# SCH_Pico-Greenhouse-PCB_2026-05-14.net
KiCad netlist of a schematic drawn in EasyEDA
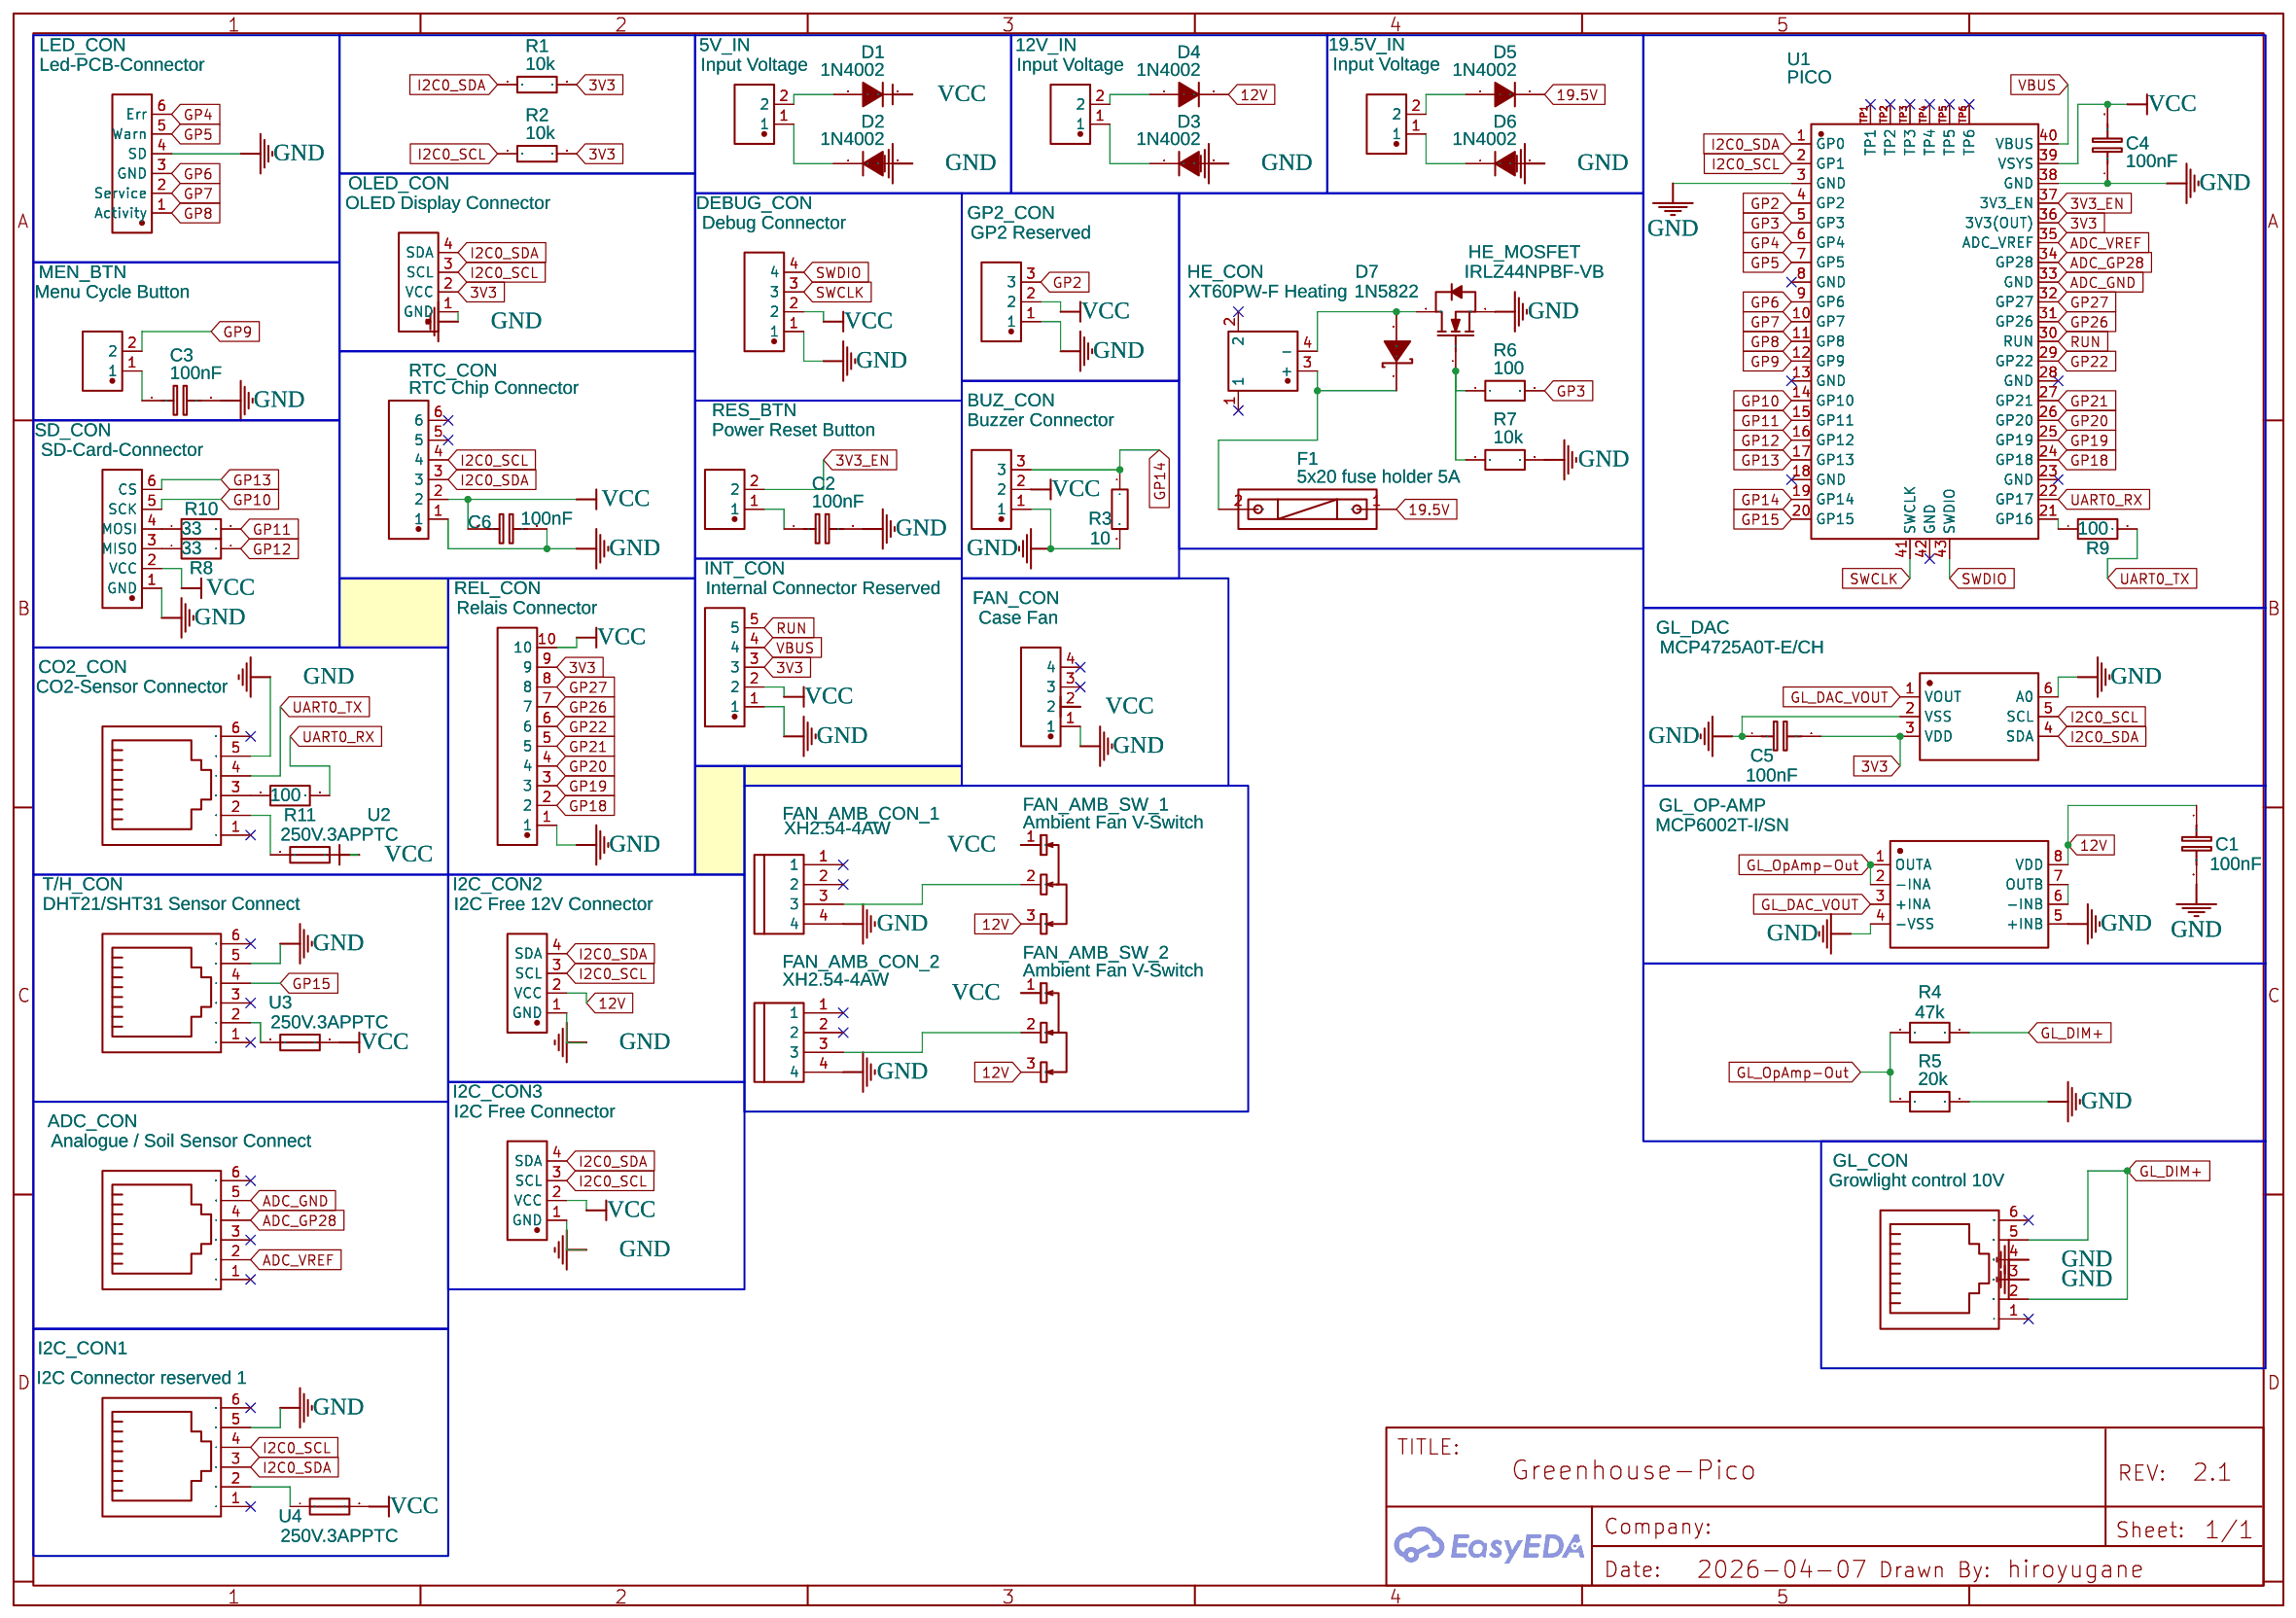
[diagram p0: schematic sheet]

(export (version "E")
  (design (tool "Eeschema 10.0.6"))
  (components
    (comp (ref "5V_IN")
      (value "Input Voltage")
      (fields (field (name "Manufacturer Part") "B2B-XH-A-BK(LF)(SN)") (field (name "Manufacturer") "JST"))
      (libsource (lib "") (part "B2B-XH-A-BK(LF)(SN)_3"))
    )
    (comp (ref "12V_IN")
      (value "Input Voltage")
      (fields (field (name "Manufacturer Part") "B2B-XH-A-BK(LF)(SN)") (field (name "Manufacturer") "JST"))
      (libsource (lib "") (part "B2B-XH-A-BK(LF)(SN)_2"))
    )
    (comp (ref "19.5V_IN")
      (value "Input Voltage")
      (fields
        (field (name "Manufacturer Part") "1935161")
        (field (name "Manufacturer") "Phoenix Contact(菲尼克斯)")
      )
      (libsource (lib "") (part "1935161"))
    )
    (comp (ref "ADC_CON")
      (value "Analogue / Soil Sensor Connect")
      (fields (field (name "Manufacturer Part") "955012661") (field (name "Manufacturer") "MOLEX"))
      (libsource (lib "") (part "95501-2661_1"))
    )
    (comp (ref "BUZ_CON")
      (value "Buzzer Connector")
      (fields (field (name "Manufacturer Part") "B3B-XH-A-BK(LF)(SN)") (field (name "Manufacturer") "JST"))
      (libsource (lib "") (part "B3B-XH-A-BK(LF)(SN)_1"))
    )
    (comp (ref "C1") (value "100nF") (libsource (lib "") (part "C_0603_EU_4")))
    (comp (ref "C2") (value "100nF") (libsource (lib "") (part "C_0603_EU_3")))
    (comp (ref "C3") (value "100nF") (libsource (lib "") (part "C_0603_EU")))
    (comp (ref "C4") (value "100nF") (libsource (lib "") (part "C_0603_EU_2")))
    (comp (ref "C5") (value "100nF") (libsource (lib "") (part "C_0603_EU_1")))
    (comp (ref "C6") (value "100nF") (libsource (lib "") (part "C_0603_EU_3")))
    (comp (ref "CO2_CON")
      (value "CO2-Sensor Connector")
      (fields (field (name "Manufacturer Part") "955012661") (field (name "Manufacturer") "MOLEX"))
      (libsource (lib "") (part "95501-2661_2"))
    )
    (comp (ref "D1")
      (value "1N4002")
      (fields (field (name "Manufacturer Part") "1N4002-E3/54") (field (name "Manufacturer") "VISHAY(威世)"))
      (libsource (lib "") (part "1N4002-E3/54"))
    )
    (comp (ref "D2")
      (value "1N4002")
      (fields (field (name "Manufacturer Part") "1N4002-E3/54") (field (name "Manufacturer") "VISHAY(威世)"))
      (libsource (lib "") (part "1N4002-E3/54_1"))
    )
    (comp (ref "D3")
      (value "1N4002")
      (fields (field (name "Manufacturer Part") "1N4002-E3/54") (field (name "Manufacturer") "VISHAY(威世)"))
      (libsource (lib "") (part "1N4002-E3/54_1"))
    )
    (comp (ref "D4")
      (value "1N4002")
      (fields (field (name "Manufacturer Part") "1N4002-E3/54") (field (name "Manufacturer") "VISHAY(威世)"))
      (libsource (lib "") (part "1N4002-E3/54"))
    )
    (comp (ref "D5")
      (value "1N4002")
      (fields (field (name "Manufacturer Part") "1N4002-E3/54") (field (name "Manufacturer") "VISHAY(威世)"))
      (libsource (lib "") (part "1N4002-E3/54"))
    )
    (comp (ref "D6")
      (value "1N4002")
      (fields (field (name "Manufacturer Part") "1N4002-E3/54") (field (name "Manufacturer") "VISHAY(威世)"))
      (libsource (lib "") (part "1N4002-E3/54_1"))
    )
    (comp (ref "D7")
      (value "1N5822")
      (fields (field (name "Manufacturer") "MDD(辰达半导体)"))
      (libsource (lib "") (part "1N5822"))
    )
    (comp (ref "DEBUG_CON")
      (value "Debug Connector")
      (fields (field (name "Manufacturer Part") "B4B-XH-A-R(LF)(SN)") (field (name "Manufacturer") "JST"))
      (libsource (lib "") (part "B4B-XH-A-R(LF)(SN)_1"))
    )
    (comp (ref "F1")
      (value "5x20 fuse holder 5A")
      (fields
        (field (name "Manufacturer Part") "5x20 BLX-A型 保险丝支架 XC-7")
        (field (name "Manufacturer") "xcfuse(旭程)")
      )
      (libsource (lib "") (part "5x20 BLX-Atype Fuse holder XC-7"))
    )
    (comp (ref "FAN_AMB_CON_1")
      (value "XH2.54-4AW")
      (fields (field (name "Manufacturer Part") "XH-4AW") (field (name "Manufacturer") "BOOMELE(博穆精密)"))
      (libsource (lib "") (part "XH2.54-4AW"))
    )
    (comp (ref "FAN_AMB_CON_2")
      (value "XH2.54-4AW")
      (fields (field (name "Manufacturer Part") "XH-4AW") (field (name "Manufacturer") "BOOMELE(博穆精密)"))
      (libsource (lib "") (part "XH2.54-4AW"))
    )
    (comp (ref "FAN_AMB_SW_1")
      (value "Ambient Fan V-Switch")
      (fields
        (field (name "Manufacturer Part") "MST-12D18G4 SPDT Slide Switch")
        (field (name "Manufacturer") "SHOU HAN(首韩)")
      )
      (libsource (lib "") (part "MST-12D18G4 SPDT SLIDE SWITCH"))
    )
    (comp (ref "FAN_AMB_SW_2")
      (value "Ambient Fan V-Switch")
      (fields
        (field (name "Manufacturer Part") "MST-12D18G4 SPDT Slide Switch")
        (field (name "Manufacturer") "SHOU HAN(首韩)")
      )
      (libsource (lib "") (part "MST-12D18G4 SPDT SLIDE SWITCH"))
    )
    (comp (ref "FAN_CON")
      (value "Case Fan")
      (fields (field (name "Manufacturer Part") "B4B-XH-A-R(LF)(SN)") (field (name "Manufacturer") "JST"))
      (libsource (lib "") (part "B4B-XH-A-R(LF)(SN)"))
    )
    (comp (ref "GL_CON")
      (value "Growlight control 10V")
      (fields (field (name "Manufacturer Part") "955012661") (field (name "Manufacturer") "MOLEX"))
      (libsource (lib "") (part "95501-2661_3"))
    )
    (comp (ref "GL_DAC")
      (value "MCP4725A0T-E/CH")
      (fields (field (name "Manufacturer") "MICROCHIP(美国微芯)"))
      (libsource (lib "") (part "MCP4725A0T-E/CH"))
    )
    (comp (ref "GL_OP-AMP")
      (value "MCP6002T-I/SN")
      (fields (field (name "Manufacturer") "MICROCHIP(美国微芯)"))
      (libsource (lib "") (part "MCP6002T-I/SN"))
    )
    (comp (ref "GP2_CON")
      (value "GP2 Reserved")
      (fields (field (name "Manufacturer Part") "B3B-XH-A-BK(LF)(SN)") (field (name "Manufacturer") "JST"))
      (libsource (lib "") (part "B3B-XH-A-BK(LF)(SN)"))
    )
    (comp (ref "HE_CON")
      (value "XT60PW-F Heating")
      (fields (field (name "Manufacturer Part") "XT60PW-F") (field (name "Manufacturer") "AMASS(艾迈斯)"))
      (libsource (lib "") (part "XT60PW-F_C428722"))
    )
    (comp (ref "HE_MOSFET")
      (value "IRLZ44NPBF-VB")
      (fields (field (name "Manufacturer") "VBsemi(微碧半导体)"))
      (libsource (lib "") (part "IRLZ44NPBF-VB"))
    )
    (comp (ref "I2C_CON1")
      (value "I2C Connector reserved 1")
      (fields (field (name "Manufacturer Part") "955012661") (field (name "Manufacturer") "MOLEX"))
      (libsource (lib "") (part "95501-2661"))
    )
    (comp (ref "I2C_CON2")
      (value "I2C Free 12V Connector")
      (fields (field (name "Manufacturer Part") "B4B-XH-A-R(LF)(SN)") (field (name "Manufacturer") "JST"))
      (libsource (lib "") (part "B4B-XH-A-R(LF)(SN)_3"))
    )
    (comp (ref "I2C_CON3")
      (value "I2C Free Connector")
      (fields (field (name "Manufacturer Part") "B4B-XH-A-R(LF)(SN)") (field (name "Manufacturer") "JST"))
      (libsource (lib "") (part "B4B-XH-A-R(LF)(SN)_3"))
    )
    (comp (ref "INT_CON")
      (value "Internal Connector Reserved")
      (fields (field (name "Manufacturer Part") "B5B-XH-A-M(LF)(SN)") (field (name "Manufacturer") "JST"))
      (libsource (lib "") (part "B5B-XH-A-M(LF)(SN)"))
    )
    (comp (ref "LED_CON")
      (value "Led-PCB-Connector")
      (fields (field (name "Manufacturer Part") "B6B-EH(LF)(SN)") (field (name "Manufacturer") "JST"))
      (libsource (lib "") (part "B6B-EH(LF)(SN)"))
    )
    (comp (ref "MEN_BTN")
      (value "Menu Cycle Button")
      (fields (field (name "Manufacturer Part") "B2B-XH-A-BK(LF)(SN)") (field (name "Manufacturer") "JST"))
      (libsource (lib "") (part "B2B-XH-A-BK(LF)(SN)_1"))
    )
    (comp (ref "OLED_CON")
      (value "OLED Display Connector")
      (fields (field (name "Manufacturer Part") "B4B-XH-A-R(LF)(SN)") (field (name "Manufacturer") "JST"))
      (libsource (lib "") (part "B4B-XH-A-R(LF)(SN)_2"))
    )
    (comp (ref "R1")
      (value "10k")
      (fields (field (name "Manufacturer") "Made in China"))
      (libsource (lib "") (part "330Ω (331) ±5%"))
    )
    (comp (ref "R2")
      (value "10k")
      (fields (field (name "Manufacturer") "Made in China"))
      (libsource (lib "") (part "330Ω (331) ±5%"))
    )
    (comp (ref "R3")
      (value "10")
      (fields (field (name "Manufacturer") "Made in China"))
      (libsource (lib "") (part "330Ω (331) ±5%_1"))
    )
    (comp (ref "R4") (value "47k") (libsource (lib "") (part "R_0603_EU")))
    (comp (ref "R5") (value "20k") (libsource (lib "") (part "R_0603_EU")))
    (comp (ref "R6") (value "100") (libsource (lib "") (part "R_0603_EU")))
    (comp (ref "R7") (value "10k") (libsource (lib "") (part "R_0603_EU_1")))
    (comp (ref "R8") (value "33") (libsource (lib "") (part "R_0603_EU")))
    (comp (ref "R9") (value "100") (libsource (lib "") (part "R_0603_EU")))
    (comp (ref "R10") (value "33") (libsource (lib "") (part "R_0603_EU")))
    (comp (ref "R11") (value "100") (libsource (lib "") (part "R_0603_EU")))
    (comp (ref "REL_CON")
      (value "Relais Connector")
      (fields (field (name "Manufacturer Part") "B10B-EH(LF)(SN)") (field (name "Manufacturer") "JST"))
      (libsource (lib "") (part "B10B-EH(LF)(SN)"))
    )
    (comp (ref "RES_BTN")
      (value "Power Reset Button")
      (fields (field (name "Manufacturer Part") "B2B-XH-A-BK(LF)(SN)") (field (name "Manufacturer") "JST"))
      (libsource (lib "") (part "B2B-XH-A-BK(LF)(SN)"))
    )
    (comp (ref "RTC_CON")
      (value "RTC Chip Connector")
      (fields
        (field (name "Manufacturer Part") "ZX-PM2.54-1-6PY")
        (field (name "Manufacturer") "Megastar(兆星)")
      )
      (libsource (lib "") (part "ZX-PM2.54-1-6PY"))
    )
    (comp (ref "SD_CON")
      (value "SD-Card-Connector")
      (fields (field (name "Manufacturer Part") "B6B-EH(LF)(SN)") (field (name "Manufacturer") "JST"))
      (libsource (lib "") (part "B6B-EH(LF)(SN)_1"))
    )
    (comp (ref "T/H_CON")
      (value "DHT21/SHT31 Sensor Connect")
      (fields (field (name "Manufacturer Part") "955012661") (field (name "Manufacturer") "MOLEX"))
      (libsource (lib "") (part "95501-2661_4"))
    )
    (comp (ref "U1")
      (value "PICO")
      (fields (field (name "Manufacturer") "Raspberry Pi(树莓派)"))
      (libsource (lib "") (part "PICO"))
    )
    (comp (ref "U2")
      (value "250V.3APPTC")
      (fields (field (name "Manufacturer Part") "30V3APPTC"))
      (libsource (lib "") (part "30V3APPTC"))
    )
    (comp (ref "U3")
      (value "250V.3APPTC")
      (fields (field (name "Manufacturer Part") "30V3APPTC"))
      (libsource (lib "") (part "30V3APPTC"))
    )
    (comp (ref "U4")
      (value "250V.3APPTC")
      (fields (field (name "Manufacturer Part") "30V3APPTC"))
      (libsource (lib "") (part "30V3APPTC"))
    )
  )
  (nets
    (net (code "1") (name "3V3") (class "Default")
      (node (ref "C5") (pin "2") (pinfunction "2_2") (pintype "unspecified"))
      (node (ref "GL_DAC") (pin "3") (pinfunction "VDD_3") (pintype "unspecified"))
      (node (ref "INT_CON") (pin "3") (pinfunction "3_3") (pintype "unspecified"))
      (node (ref "OLED_CON") (pin "2") (pinfunction "VCC_2") (pintype "unspecified"))
      (node (ref "R1") (pin "2") (pinfunction "2_2") (pintype "unspecified"))
      (node (ref "R2") (pin "2") (pinfunction "2_2") (pintype "unspecified"))
      (node (ref "REL_CON") (pin "9") (pinfunction "9_9") (pintype "unspecified"))
      (node (ref "U1") (pin "36") (pinfunction "3V3(OUT)_36") (pintype "unspecified"))
    )
    (net (code "2") (name "3V3_EN") (class "Default")
      (node (ref "RES_BTN") (pin "2") (pinfunction "2_2") (pintype "unspecified"))
      (node (ref "U1") (pin "37") (pinfunction "3V3_EN_37") (pintype "unspecified"))
    )
    (net (code "3") (name "12V") (class "Default")
      (node (ref "C1") (pin "1") (pinfunction "1_1") (pintype "unspecified"))
      (node (ref "D4") (pin "1") (pinfunction "C_1") (pintype "unspecified"))
      (node (ref "FAN_AMB_SW_1") (pin "3") (pinfunction "3_3") (pintype "unspecified"))
      (node (ref "FAN_AMB_SW_2") (pin "3") (pinfunction "3_3") (pintype "unspecified"))
      (node (ref "GL_OP-AMP") (pin "8") (pinfunction "VDD_8") (pintype "unspecified"))
      (node (ref "I2C_CON2") (pin "2") (pinfunction "VCC_2") (pintype "unspecified"))
    )
    (net (code "4") (name "19.5V") (class "Default")
      (node (ref "D5") (pin "1") (pinfunction "C_1") (pintype "unspecified"))
      (node (ref "F1") (pin "1") (pinfunction "1_1") (pintype "unspecified"))
    )
    (net (code "5") (name "ADC_GND") (class "Default")
      (node (ref "ADC_CON") (pin "5") (pinfunction "5_5") (pintype "unspecified"))
      (node (ref "U1") (pin "33") (pinfunction "GND_33") (pintype "unspecified"))
    )
    (net (code "6") (name "ADC_GP28") (class "Default")
      (node (ref "ADC_CON") (pin "4") (pinfunction "4_4") (pintype "unspecified"))
      (node (ref "U1") (pin "34") (pinfunction "GP28_34") (pintype "unspecified"))
    )
    (net (code "7") (name "ADC_VREF") (class "Default")
      (node (ref "ADC_CON") (pin "2") (pinfunction "2_2") (pintype "unspecified"))
      (node (ref "U1") (pin "35") (pinfunction "ADC_VREF_35") (pintype "unspecified"))
    )
    (net (code "8") (name "GL_DAC_VOUT") (class "Default")
      (node (ref "GL_DAC") (pin "1") (pinfunction "VOUT_1") (pintype "unspecified"))
      (node (ref "GL_OP-AMP") (pin "3") (pinfunction "+INA_3") (pintype "unspecified"))
    )
    (net (code "9") (name "GL_DIM+") (class "Default")
      (node (ref "GL_CON") (pin "2") (pinfunction "GL+_2") (pintype "unspecified"))
      (node (ref "GL_CON") (pin "5") (pinfunction "GL+_5") (pintype "unspecified"))
      (node (ref "R4") (pin "2") (pinfunction "2_2") (pintype "unspecified"))
    )
    (net (code "10") (name "GL_OpAmp-Out") (class "Default")
      (node (ref "GL_OP-AMP") (pin "1") (pinfunction "OUTA_1") (pintype "unspecified"))
      (node (ref "GL_OP-AMP") (pin "2") (pinfunction "-INA_2") (pintype "unspecified"))
      (node (ref "R4") (pin "1") (pinfunction "1_1") (pintype "unspecified"))
      (node (ref "R5") (pin "1") (pinfunction "1_1") (pintype "unspecified"))
    )
    (net (code "11") (name "GND") (class "Default")
      (node (ref "BUZ_CON") (pin "1") (pinfunction "1_1") (pintype "unspecified"))
      (node (ref "C1") (pin "2") (pinfunction "2_2") (pintype "unspecified"))
      (node (ref "C2") (pin "2") (pinfunction "2_2") (pintype "unspecified"))
      (node (ref "C3") (pin "2") (pinfunction "2_2") (pintype "unspecified"))
      (node (ref "C4") (pin "1") (pinfunction "1_1") (pintype "unspecified"))
      (node (ref "C5") (pin "1") (pinfunction "1_1") (pintype "unspecified"))
      (node (ref "C6") (pin "2") (pinfunction "2_2") (pintype "unspecified"))
      (node (ref "CO2_CON") (pin "5") (pinfunction "5_5") (pintype "unspecified"))
      (node (ref "D2") (pin "2") (pinfunction "A_2") (pintype "unspecified"))
      (node (ref "D3") (pin "2") (pinfunction "A_2") (pintype "unspecified"))
      (node (ref "D6") (pin "2") (pinfunction "A_2") (pintype "unspecified"))
      (node (ref "DEBUG_CON") (pin "1") (pinfunction "1_1") (pintype "unspecified"))
      (node (ref "FAN_AMB_CON_1") (pin "4") (pinfunction "4_4") (pintype "unspecified"))
      (node (ref "FAN_AMB_CON_2") (pin "4") (pinfunction "4_4") (pintype "unspecified"))
      (node (ref "FAN_CON") (pin "1") (pinfunction "1_1") (pintype "unspecified"))
      (node (ref "GL_CON") (pin "3") (pinfunction "GL-_3") (pintype "unspecified"))
      (node (ref "GL_CON") (pin "4") (pinfunction "GL-_4") (pintype "unspecified"))
      (node (ref "GL_DAC") (pin "2") (pinfunction "VSS_2") (pintype "unspecified"))
      (node (ref "GL_DAC") (pin "6") (pinfunction "A0_6") (pintype "unspecified"))
      (node (ref "GL_OP-AMP") (pin "4") (pinfunction "-VSS_4") (pintype "unspecified"))
      (node (ref "GL_OP-AMP") (pin "5") (pinfunction "+INB_5") (pintype "unspecified"))
      (node (ref "GP2_CON") (pin "1") (pinfunction "1_1") (pintype "unspecified"))
      (node (ref "HE_MOSFET") (pin "3") (pinfunction "S_3") (pintype "unspecified"))
      (node (ref "I2C_CON1") (pin "5") (pinfunction "5_5") (pintype "unspecified"))
      (node (ref "I2C_CON2") (pin "1") (pinfunction "GND_1") (pintype "unspecified"))
      (node (ref "I2C_CON3") (pin "1") (pinfunction "GND_1") (pintype "unspecified"))
      (node (ref "INT_CON") (pin "1") (pinfunction "1_1") (pintype "unspecified"))
      (node (ref "LED_CON") (pin "4") (pinfunction "SD_4") (pintype "unspecified"))
      (node (ref "OLED_CON") (pin "1") (pinfunction "GND_1") (pintype "unspecified"))
      (node (ref "R3") (pin "2") (pinfunction "2_2") (pintype "unspecified"))
      (node (ref "R5") (pin "2") (pinfunction "2_2") (pintype "unspecified"))
      (node (ref "R7") (pin "1") (pinfunction "1_1") (pintype "unspecified"))
      (node (ref "REL_CON") (pin "1") (pinfunction "1_1") (pintype "unspecified"))
      (node (ref "RTC_CON") (pin "1") (pinfunction "1_1") (pintype "unspecified"))
      (node (ref "SD_CON") (pin "1") (pinfunction "GND_1") (pintype "unspecified"))
      (node (ref "T/H_CON") (pin "5") (pinfunction "5_5") (pintype "unspecified"))
      (node (ref "U1") (pin "3") (pinfunction "GND_3") (pintype "unspecified"))
      (node (ref "U1") (pin "38") (pinfunction "GND_38") (pintype "unspecified"))
    )
    (net (code "12") (name "GP2") (class "Default")
      (node (ref "GP2_CON") (pin "3") (pinfunction "3_3") (pintype "unspecified"))
      (node (ref "U1") (pin "4") (pinfunction "GP2_4") (pintype "unspecified"))
    )
    (net (code "13") (name "GP3") (class "Default")
      (node (ref "R6") (pin "2") (pinfunction "2_2") (pintype "unspecified"))
      (node (ref "U1") (pin "5") (pinfunction "GP3_5") (pintype "unspecified"))
    )
    (net (code "14") (name "GP4") (class "Default")
      (node (ref "LED_CON") (pin "6") (pinfunction "Err_6") (pintype "unspecified"))
      (node (ref "U1") (pin "6") (pinfunction "GP4_6") (pintype "unspecified"))
    )
    (net (code "15") (name "GP5") (class "Default")
      (node (ref "LED_CON") (pin "5") (pinfunction "Warn_5") (pintype "unspecified"))
      (node (ref "U1") (pin "7") (pinfunction "GP5_7") (pintype "unspecified"))
    )
    (net (code "16") (name "GP6") (class "Default")
      (node (ref "LED_CON") (pin "3") (pinfunction "GND_3") (pintype "unspecified"))
      (node (ref "U1") (pin "9") (pinfunction "GP6_9") (pintype "unspecified"))
    )
    (net (code "17") (name "GP7") (class "Default")
      (node (ref "LED_CON") (pin "2") (pinfunction "Service_2") (pintype "unspecified"))
      (node (ref "U1") (pin "10") (pinfunction "GP7_10") (pintype "unspecified"))
    )
    (net (code "18") (name "GP8") (class "Default")
      (node (ref "LED_CON") (pin "1") (pinfunction "Activity_1") (pintype "unspecified"))
      (node (ref "U1") (pin "11") (pinfunction "GP8_11") (pintype "unspecified"))
    )
    (net (code "19") (name "GP9") (class "Default")
      (node (ref "MEN_BTN") (pin "2") (pinfunction "2_2") (pintype "unspecified"))
      (node (ref "U1") (pin "12") (pinfunction "GP9_12") (pintype "unspecified"))
    )
    (net (code "20") (name "GP10") (class "Default")
      (node (ref "SD_CON") (pin "5") (pinfunction "SCK_5") (pintype "unspecified"))
      (node (ref "U1") (pin "14") (pinfunction "GP10_14") (pintype "unspecified"))
    )
    (net (code "21") (name "GP11") (class "Default")
      (node (ref "R10") (pin "2") (pinfunction "2_2") (pintype "unspecified"))
      (node (ref "U1") (pin "15") (pinfunction "GP11_15") (pintype "unspecified"))
    )
    (net (code "22") (name "GP12") (class "Default")
      (node (ref "R8") (pin "2") (pinfunction "2_2") (pintype "unspecified"))
      (node (ref "U1") (pin "16") (pinfunction "GP12_16") (pintype "unspecified"))
    )
    (net (code "23") (name "GP13") (class "Default")
      (node (ref "SD_CON") (pin "6") (pinfunction "CS_6") (pintype "unspecified"))
      (node (ref "U1") (pin "17") (pinfunction "GP13_17") (pintype "unspecified"))
    )
    (net (code "24") (name "GP14") (class "Default")
      (node (ref "BUZ_CON") (pin "3") (pinfunction "3_3") (pintype "unspecified"))
      (node (ref "R3") (pin "1") (pinfunction "1_1") (pintype "unspecified"))
      (node (ref "U1") (pin "19") (pinfunction "GP14_19") (pintype "unspecified"))
    )
    (net (code "25") (name "GP15") (class "Default")
      (node (ref "T/H_CON") (pin "4") (pinfunction "4_4") (pintype "unspecified"))
      (node (ref "U1") (pin "20") (pinfunction "GP15_20") (pintype "unspecified"))
    )
    (net (code "26") (name "GP18") (class "Default")
      (node (ref "REL_CON") (pin "2") (pinfunction "2_2") (pintype "unspecified"))
      (node (ref "U1") (pin "24") (pinfunction "GP18_24") (pintype "unspecified"))
    )
    (net (code "27") (name "GP19") (class "Default")
      (node (ref "REL_CON") (pin "3") (pinfunction "3_3") (pintype "unspecified"))
      (node (ref "U1") (pin "25") (pinfunction "GP19_25") (pintype "unspecified"))
    )
    (net (code "28") (name "GP20") (class "Default")
      (node (ref "REL_CON") (pin "4") (pinfunction "4_4") (pintype "unspecified"))
      (node (ref "U1") (pin "26") (pinfunction "GP20_26") (pintype "unspecified"))
    )
    (net (code "29") (name "GP21") (class "Default")
      (node (ref "REL_CON") (pin "5") (pinfunction "5_5") (pintype "unspecified"))
      (node (ref "U1") (pin "27") (pinfunction "GP21_27") (pintype "unspecified"))
    )
    (net (code "30") (name "GP22") (class "Default")
      (node (ref "REL_CON") (pin "6") (pinfunction "6_6") (pintype "unspecified"))
      (node (ref "U1") (pin "29") (pinfunction "GP22_29") (pintype "unspecified"))
    )
    (net (code "31") (name "GP26") (class "Default")
      (node (ref "REL_CON") (pin "7") (pinfunction "7_7") (pintype "unspecified"))
      (node (ref "U1") (pin "31") (pinfunction "GP26_31") (pintype "unspecified"))
    )
    (net (code "32") (name "GP27") (class "Default")
      (node (ref "REL_CON") (pin "8") (pinfunction "8_8") (pintype "unspecified"))
      (node (ref "U1") (pin "32") (pinfunction "GP27_32") (pintype "unspecified"))
    )
    (net (code "33") (name "I2C0_SCL") (class "Default")
      (node (ref "GL_DAC") (pin "5") (pinfunction "SCL_5") (pintype "unspecified"))
      (node (ref "I2C_CON1") (pin "4") (pinfunction "4_4") (pintype "unspecified"))
      (node (ref "I2C_CON2") (pin "3") (pinfunction "SCL_3") (pintype "unspecified"))
      (node (ref "I2C_CON3") (pin "3") (pinfunction "SCL_3") (pintype "unspecified"))
      (node (ref "OLED_CON") (pin "3") (pinfunction "SCL_3") (pintype "unspecified"))
      (node (ref "R2") (pin "1") (pinfunction "1_1") (pintype "unspecified"))
      (node (ref "RTC_CON") (pin "4") (pinfunction "4_4") (pintype "unspecified"))
      (node (ref "U1") (pin "2") (pinfunction "GP1_2") (pintype "unspecified"))
    )
    (net (code "34") (name "I2C0_SDA") (class "Default")
      (node (ref "GL_DAC") (pin "4") (pinfunction "SDA_4") (pintype "unspecified"))
      (node (ref "I2C_CON1") (pin "3") (pinfunction "3_3") (pintype "unspecified"))
      (node (ref "I2C_CON2") (pin "4") (pinfunction "SDA_4") (pintype "unspecified"))
      (node (ref "I2C_CON3") (pin "4") (pinfunction "SDA_4") (pintype "unspecified"))
      (node (ref "OLED_CON") (pin "4") (pinfunction "SDA_4") (pintype "unspecified"))
      (node (ref "R1") (pin "1") (pinfunction "1_1") (pintype "unspecified"))
      (node (ref "RTC_CON") (pin "3") (pinfunction "3_3") (pintype "unspecified"))
      (node (ref "U1") (pin "1") (pinfunction "GP0_1") (pintype "unspecified"))
    )
    (net (code "35") (name "Net-(C2-Pad1)") (class "Default")
      (node (ref "C2") (pin "1") (pinfunction "1_1") (pintype "unspecified"))
      (node (ref "RES_BTN") (pin "1") (pinfunction "1_1") (pintype "unspecified"))
    )
    (net (code "36") (name "Net-(C3-Pad1)") (class "Default")
      (node (ref "C3") (pin "1") (pinfunction "1_1") (pintype "unspecified"))
      (node (ref "MEN_BTN") (pin "1") (pinfunction "1_1") (pintype "unspecified"))
    )
    (net (code "37") (name "Net-(CO2_CON-Pad2)") (class "Default")
      (node (ref "CO2_CON") (pin "2") (pinfunction "2_2") (pintype "unspecified"))
      (node (ref "U2") (pin "1") (pinfunction "1_1") (pintype "unspecified"))
    )
    (net (code "38") (name "Net-(CO2_CON-Pad3)") (class "Default")
      (node (ref "CO2_CON") (pin "3") (pinfunction "3_3") (pintype "unspecified"))
      (node (ref "R11") (pin "1") (pinfunction "1_1") (pintype "unspecified"))
    )
    (net (code "39") (name "Net-(D1-A)") (class "Default")
      (node (ref "5V_IN") (pin "2") (pinfunction "2_2") (pintype "unspecified"))
      (node (ref "D1") (pin "2") (pinfunction "A_2") (pintype "unspecified"))
    )
    (net (code "40") (name "Net-(D2-C)") (class "Default")
      (node (ref "5V_IN") (pin "1") (pinfunction "1_1") (pintype "unspecified"))
      (node (ref "D2") (pin "1") (pinfunction "C_1") (pintype "unspecified"))
    )
    (net (code "41") (name "Net-(D3-C)") (class "Default")
      (node (ref "12V_IN") (pin "1") (pinfunction "1_1") (pintype "unspecified"))
      (node (ref "D3") (pin "1") (pinfunction "C_1") (pintype "unspecified"))
    )
    (net (code "42") (name "Net-(D4-A)") (class "Default")
      (node (ref "12V_IN") (pin "2") (pinfunction "2_2") (pintype "unspecified"))
      (node (ref "D4") (pin "2") (pinfunction "A_2") (pintype "unspecified"))
    )
    (net (code "43") (name "Net-(D5-A)") (class "Default")
      (node (ref "19.5V_IN") (pin "2") (pinfunction "2_2") (pintype "unspecified"))
      (node (ref "D5") (pin "2") (pinfunction "A_2") (pintype "unspecified"))
    )
    (net (code "44") (name "Net-(D6-C)") (class "Default")
      (node (ref "19.5V_IN") (pin "1") (pinfunction "1_1") (pintype "unspecified"))
      (node (ref "D6") (pin "1") (pinfunction "C_1") (pintype "unspecified"))
    )
    (net (code "45") (name "Net-(D7-A)") (class "Default")
      (node (ref "D7") (pin "1") (pinfunction "A_1") (pintype "unspecified"))
      (node (ref "HE_CON") (pin "4") (pinfunction "-_4") (pintype "unspecified"))
      (node (ref "HE_MOSFET") (pin "2") (pinfunction "D_2") (pintype "unspecified"))
    )
    (net (code "46") (name "Net-(D7-K)") (class "Default")
      (node (ref "D7") (pin "2") (pinfunction "K_2") (pintype "unspecified"))
      (node (ref "F1") (pin "2") (pinfunction "2_2") (pintype "unspecified"))
      (node (ref "HE_CON") (pin "3") (pinfunction "+_3") (pintype "unspecified"))
    )
    (net (code "47") (name "Net-(FAN_AMB_CON_1-Pad3)") (class "Default")
      (node (ref "FAN_AMB_CON_1") (pin "3") (pinfunction "3_3") (pintype "unspecified"))
      (node (ref "FAN_AMB_SW_1") (pin "2") (pinfunction "2_2") (pintype "unspecified"))
    )
    (net (code "48") (name "Net-(FAN_AMB_CON_2-Pad3)") (class "Default")
      (node (ref "FAN_AMB_CON_2") (pin "3") (pinfunction "3_3") (pintype "unspecified"))
      (node (ref "FAN_AMB_SW_2") (pin "2") (pinfunction "2_2") (pintype "unspecified"))
    )
    (net (code "49") (name "Net-(GL_OP-AMP--INB)") (class "Default")
      (node (ref "GL_OP-AMP") (pin "6") (pinfunction "-INB_6") (pintype "unspecified"))
      (node (ref "GL_OP-AMP") (pin "7") (pinfunction "OUTB_7") (pintype "unspecified"))
    )
    (net (code "50") (name "Net-(HE_MOSFET-G)") (class "Default")
      (node (ref "HE_MOSFET") (pin "1") (pinfunction "G_1") (pintype "unspecified"))
      (node (ref "R6") (pin "1") (pinfunction "1_1") (pintype "unspecified"))
      (node (ref "R7") (pin "2") (pinfunction "2_2") (pintype "unspecified"))
    )
    (net (code "51") (name "Net-(I2C_CON1-Pad2)") (class "Default")
      (node (ref "I2C_CON1") (pin "2") (pinfunction "2_2") (pintype "unspecified"))
      (node (ref "U4") (pin "1") (pinfunction "1_1") (pintype "unspecified"))
    )
    (net (code "52") (name "Net-(SD_CON-MISO)") (class "Default")
      (node (ref "R8") (pin "1") (pinfunction "1_1") (pintype "unspecified"))
      (node (ref "SD_CON") (pin "3") (pinfunction "MISO_3") (pintype "unspecified"))
    )
    (net (code "53") (name "Net-(SD_CON-MOSI)") (class "Default")
      (node (ref "R10") (pin "1") (pinfunction "1_1") (pintype "unspecified"))
      (node (ref "SD_CON") (pin "4") (pinfunction "MOSI_4") (pintype "unspecified"))
    )
    (net (code "54") (name "Net-(T/H_CON-Pad2)") (class "Default")
      (node (ref "T/H_CON") (pin "2") (pinfunction "2_2") (pintype "unspecified"))
      (node (ref "U3") (pin "1") (pinfunction "1_1") (pintype "unspecified"))
    )
    (net (code "55") (name "Net-(U1-GP16)") (class "Default")
      (node (ref "R9") (pin "1") (pinfunction "1_1") (pintype "unspecified"))
      (node (ref "U1") (pin "21") (pinfunction "GP16_21") (pintype "unspecified"))
    )
    (net (code "56") (name "RUN") (class "Default")
      (node (ref "INT_CON") (pin "5") (pinfunction "5_5") (pintype "unspecified"))
      (node (ref "U1") (pin "30") (pinfunction "RUN_30") (pintype "unspecified"))
    )
    (net (code "57") (name "SWCLK") (class "Default")
      (node (ref "DEBUG_CON") (pin "3") (pinfunction "3_3") (pintype "unspecified"))
      (node (ref "U1") (pin "41") (pinfunction "SWCLK_41") (pintype "unspecified"))
    )
    (net (code "58") (name "SWDIO") (class "Default")
      (node (ref "DEBUG_CON") (pin "4") (pinfunction "4_4") (pintype "unspecified"))
      (node (ref "U1") (pin "43") (pinfunction "SWDIO_43") (pintype "unspecified"))
    )
    (net (code "59") (name "UART0_RX") (class "Default")
      (node (ref "R11") (pin "2") (pinfunction "2_2") (pintype "unspecified"))
      (node (ref "U1") (pin "22") (pinfunction "GP17_22") (pintype "unspecified"))
    )
    (net (code "60") (name "UART0_TX") (class "Default")
      (node (ref "CO2_CON") (pin "4") (pinfunction "4_4") (pintype "unspecified"))
      (node (ref "R9") (pin "2") (pinfunction "2_2") (pintype "unspecified"))
    )
    (net (code "61") (name "VBUS") (class "Default")
      (node (ref "INT_CON") (pin "4") (pinfunction "4_4") (pintype "unspecified"))
      (node (ref "U1") (pin "40") (pinfunction "VBUS_40") (pintype "unspecified"))
    )
    (net (code "62") (name "VCC") (class "Default")
      (node (ref "BUZ_CON") (pin "2") (pinfunction "2_2") (pintype "unspecified"))
      (node (ref "C4") (pin "2") (pinfunction "2_2") (pintype "unspecified"))
      (node (ref "C6") (pin "1") (pinfunction "1_1") (pintype "unspecified"))
      (node (ref "D1") (pin "1") (pinfunction "C_1") (pintype "unspecified"))
      (node (ref "DEBUG_CON") (pin "2") (pinfunction "2_2") (pintype "unspecified"))
      (node (ref "FAN_AMB_SW_1") (pin "1") (pinfunction "1_1") (pintype "unspecified"))
      (node (ref "FAN_AMB_SW_2") (pin "1") (pinfunction "1_1") (pintype "unspecified"))
      (node (ref "FAN_CON") (pin "2") (pinfunction "2_2") (pintype "unspecified"))
      (node (ref "GP2_CON") (pin "2") (pinfunction "2_2") (pintype "unspecified"))
      (node (ref "I2C_CON3") (pin "2") (pinfunction "VCC_2") (pintype "unspecified"))
      (node (ref "INT_CON") (pin "2") (pinfunction "2_2") (pintype "unspecified"))
      (node (ref "REL_CON") (pin "10") (pinfunction "10_10") (pintype "unspecified"))
      (node (ref "RTC_CON") (pin "2") (pinfunction "2_2") (pintype "unspecified"))
      (node (ref "SD_CON") (pin "2") (pinfunction "VCC_2") (pintype "unspecified"))
      (node (ref "U1") (pin "39") (pinfunction "VSYS_39") (pintype "unspecified"))
      (node (ref "U2") (pin "2") (pinfunction "2_2") (pintype "unspecified"))
      (node (ref "U3") (pin "2") (pinfunction "2_2") (pintype "unspecified"))
      (node (ref "U4") (pin "2") (pinfunction "2_2") (pintype "unspecified"))
    )
    (net (code "63") (name "unconnected-(ADC_CON-Pad1)") (class "Default")
      (node (ref "ADC_CON") (pin "1") (pinfunction "1_1") (pintype "unspecified+no_connect"))
    )
    (net (code "64") (name "unconnected-(ADC_CON-Pad3)") (class "Default")
      (node (ref "ADC_CON") (pin "3") (pinfunction "3_3") (pintype "unspecified+no_connect"))
    )
    (net (code "65") (name "unconnected-(ADC_CON-Pad6)") (class "Default")
      (node (ref "ADC_CON") (pin "6") (pinfunction "6_6") (pintype "unspecified+no_connect"))
    )
    (net (code "66") (name "unconnected-(CO2_CON-Pad1)") (class "Default")
      (node (ref "CO2_CON") (pin "1") (pinfunction "1_1") (pintype "unspecified+no_connect"))
    )
    (net (code "67") (name "unconnected-(CO2_CON-Pad6)") (class "Default")
      (node (ref "CO2_CON") (pin "6") (pinfunction "6_6") (pintype "unspecified+no_connect"))
    )
    (net (code "68") (name "unconnected-(FAN_AMB_CON_1-Pad1)") (class "Default")
      (node (ref "FAN_AMB_CON_1") (pin "1") (pinfunction "1_1") (pintype "unspecified+no_connect"))
    )
    (net (code "69") (name "unconnected-(FAN_AMB_CON_1-Pad2)") (class "Default")
      (node (ref "FAN_AMB_CON_1") (pin "2") (pinfunction "2_2") (pintype "unspecified+no_connect"))
    )
    (net (code "70") (name "unconnected-(FAN_AMB_CON_2-Pad1)") (class "Default")
      (node (ref "FAN_AMB_CON_2") (pin "1") (pinfunction "1_1") (pintype "unspecified+no_connect"))
    )
    (net (code "71") (name "unconnected-(FAN_AMB_CON_2-Pad2)") (class "Default")
      (node (ref "FAN_AMB_CON_2") (pin "2") (pinfunction "2_2") (pintype "unspecified+no_connect"))
    )
    (net (code "72") (name "unconnected-(FAN_CON-Pad3)") (class "Default")
      (node (ref "FAN_CON") (pin "3") (pinfunction "3_3") (pintype "unspecified+no_connect"))
    )
    (net (code "73") (name "unconnected-(FAN_CON-Pad4)") (class "Default")
      (node (ref "FAN_CON") (pin "4") (pinfunction "4_4") (pintype "unspecified+no_connect"))
    )
    (net (code "74") (name "unconnected-(GL_CON-Pad1)") (class "Default")
      (node (ref "GL_CON") (pin "1") (pinfunction "1_1") (pintype "unspecified+no_connect"))
    )
    (net (code "75") (name "unconnected-(GL_CON-Pad6)") (class "Default")
      (node (ref "GL_CON") (pin "6") (pinfunction "6_6") (pintype "unspecified+no_connect"))
    )
    (net (code "76") (name "unconnected-(HE_CON-Pad1)") (class "Default")
      (node (ref "HE_CON") (pin "1") (pinfunction "1_1") (pintype "unspecified+no_connect"))
    )
    (net (code "77") (name "unconnected-(HE_CON-Pad2)") (class "Default")
      (node (ref "HE_CON") (pin "2") (pinfunction "2_2") (pintype "unspecified+no_connect"))
    )
    (net (code "78") (name "unconnected-(I2C_CON1-Pad1)") (class "Default")
      (node (ref "I2C_CON1") (pin "1") (pinfunction "1_1") (pintype "unspecified+no_connect"))
    )
    (net (code "79") (name "unconnected-(I2C_CON1-Pad6)") (class "Default")
      (node (ref "I2C_CON1") (pin "6") (pinfunction "6_6") (pintype "unspecified+no_connect"))
    )
    (net (code "80") (name "unconnected-(RTC_CON-Pad5)") (class "Default")
      (node (ref "RTC_CON") (pin "5") (pinfunction "5_5") (pintype "unspecified+no_connect"))
    )
    (net (code "81") (name "unconnected-(RTC_CON-Pad6)") (class "Default")
      (node (ref "RTC_CON") (pin "6") (pinfunction "6_6") (pintype "unspecified+no_connect"))
    )
    (net (code "82") (name "unconnected-(T/H_CON-Pad1)") (class "Default")
      (node (ref "T/H_CON") (pin "1") (pinfunction "1_1") (pintype "unspecified+no_connect"))
    )
    (net (code "83") (name "unconnected-(T/H_CON-Pad3)") (class "Default")
      (node (ref "T/H_CON") (pin "3") (pinfunction "3_3") (pintype "unspecified+no_connect"))
    )
    (net (code "84") (name "unconnected-(T/H_CON-Pad6)") (class "Default")
      (node (ref "T/H_CON") (pin "6") (pinfunction "6_6") (pintype "unspecified+no_connect"))
    )
    (net (code "85") (name "unconnected-(U1-GND-Pad8)") (class "Default")
      (node (ref "U1") (pin "8") (pinfunction "GND_8") (pintype "unspecified+no_connect"))
    )
    (net (code "86") (name "unconnected-(U1-GND-Pad13)") (class "Default")
      (node (ref "U1") (pin "13") (pinfunction "GND_13") (pintype "unspecified+no_connect"))
    )
    (net (code "87") (name "unconnected-(U1-GND-Pad18)") (class "Default")
      (node (ref "U1") (pin "18") (pinfunction "GND_18") (pintype "unspecified+no_connect"))
    )
    (net (code "88") (name "unconnected-(U1-GND-Pad23)") (class "Default")
      (node (ref "U1") (pin "23") (pinfunction "GND_23") (pintype "unspecified+no_connect"))
    )
    (net (code "89") (name "unconnected-(U1-GND-Pad28)") (class "Default")
      (node (ref "U1") (pin "28") (pinfunction "GND_28") (pintype "unspecified+no_connect"))
    )
    (net (code "90") (name "unconnected-(U1-GND-Pad42)") (class "Default")
      (node (ref "U1") (pin "42") (pinfunction "GND_42") (pintype "unspecified+no_connect"))
    )
    (net (code "91") (name "unconnected-(U1-PadTP1)") (class "Default")
      (node (ref "U1") (pin "TP1") (pinfunction "TP1_TP1") (pintype "unspecified+no_connect"))
    )
    (net (code "92") (name "unconnected-(U1-PadTP2)") (class "Default")
      (node (ref "U1") (pin "TP2") (pinfunction "TP2_TP2") (pintype "unspecified+no_connect"))
    )
    (net (code "93") (name "unconnected-(U1-PadTP3)") (class "Default")
      (node (ref "U1") (pin "TP3") (pinfunction "TP3_TP3") (pintype "unspecified+no_connect"))
    )
    (net (code "94") (name "unconnected-(U1-PadTP4)") (class "Default")
      (node (ref "U1") (pin "TP4") (pinfunction "TP4_TP4") (pintype "unspecified+no_connect"))
    )
    (net (code "95") (name "unconnected-(U1-PadTP5)") (class "Default")
      (node (ref "U1") (pin "TP5") (pinfunction "TP5_TP5") (pintype "unspecified+no_connect"))
    )
    (net (code "96") (name "unconnected-(U1-PadTP6)") (class "Default")
      (node (ref "U1") (pin "TP6") (pinfunction "TP6_TP6") (pintype "unspecified+no_connect"))
    )
  )
)
